# PA_stage_2.net
KiCad netlist of a schematic drawn in Altium Designer
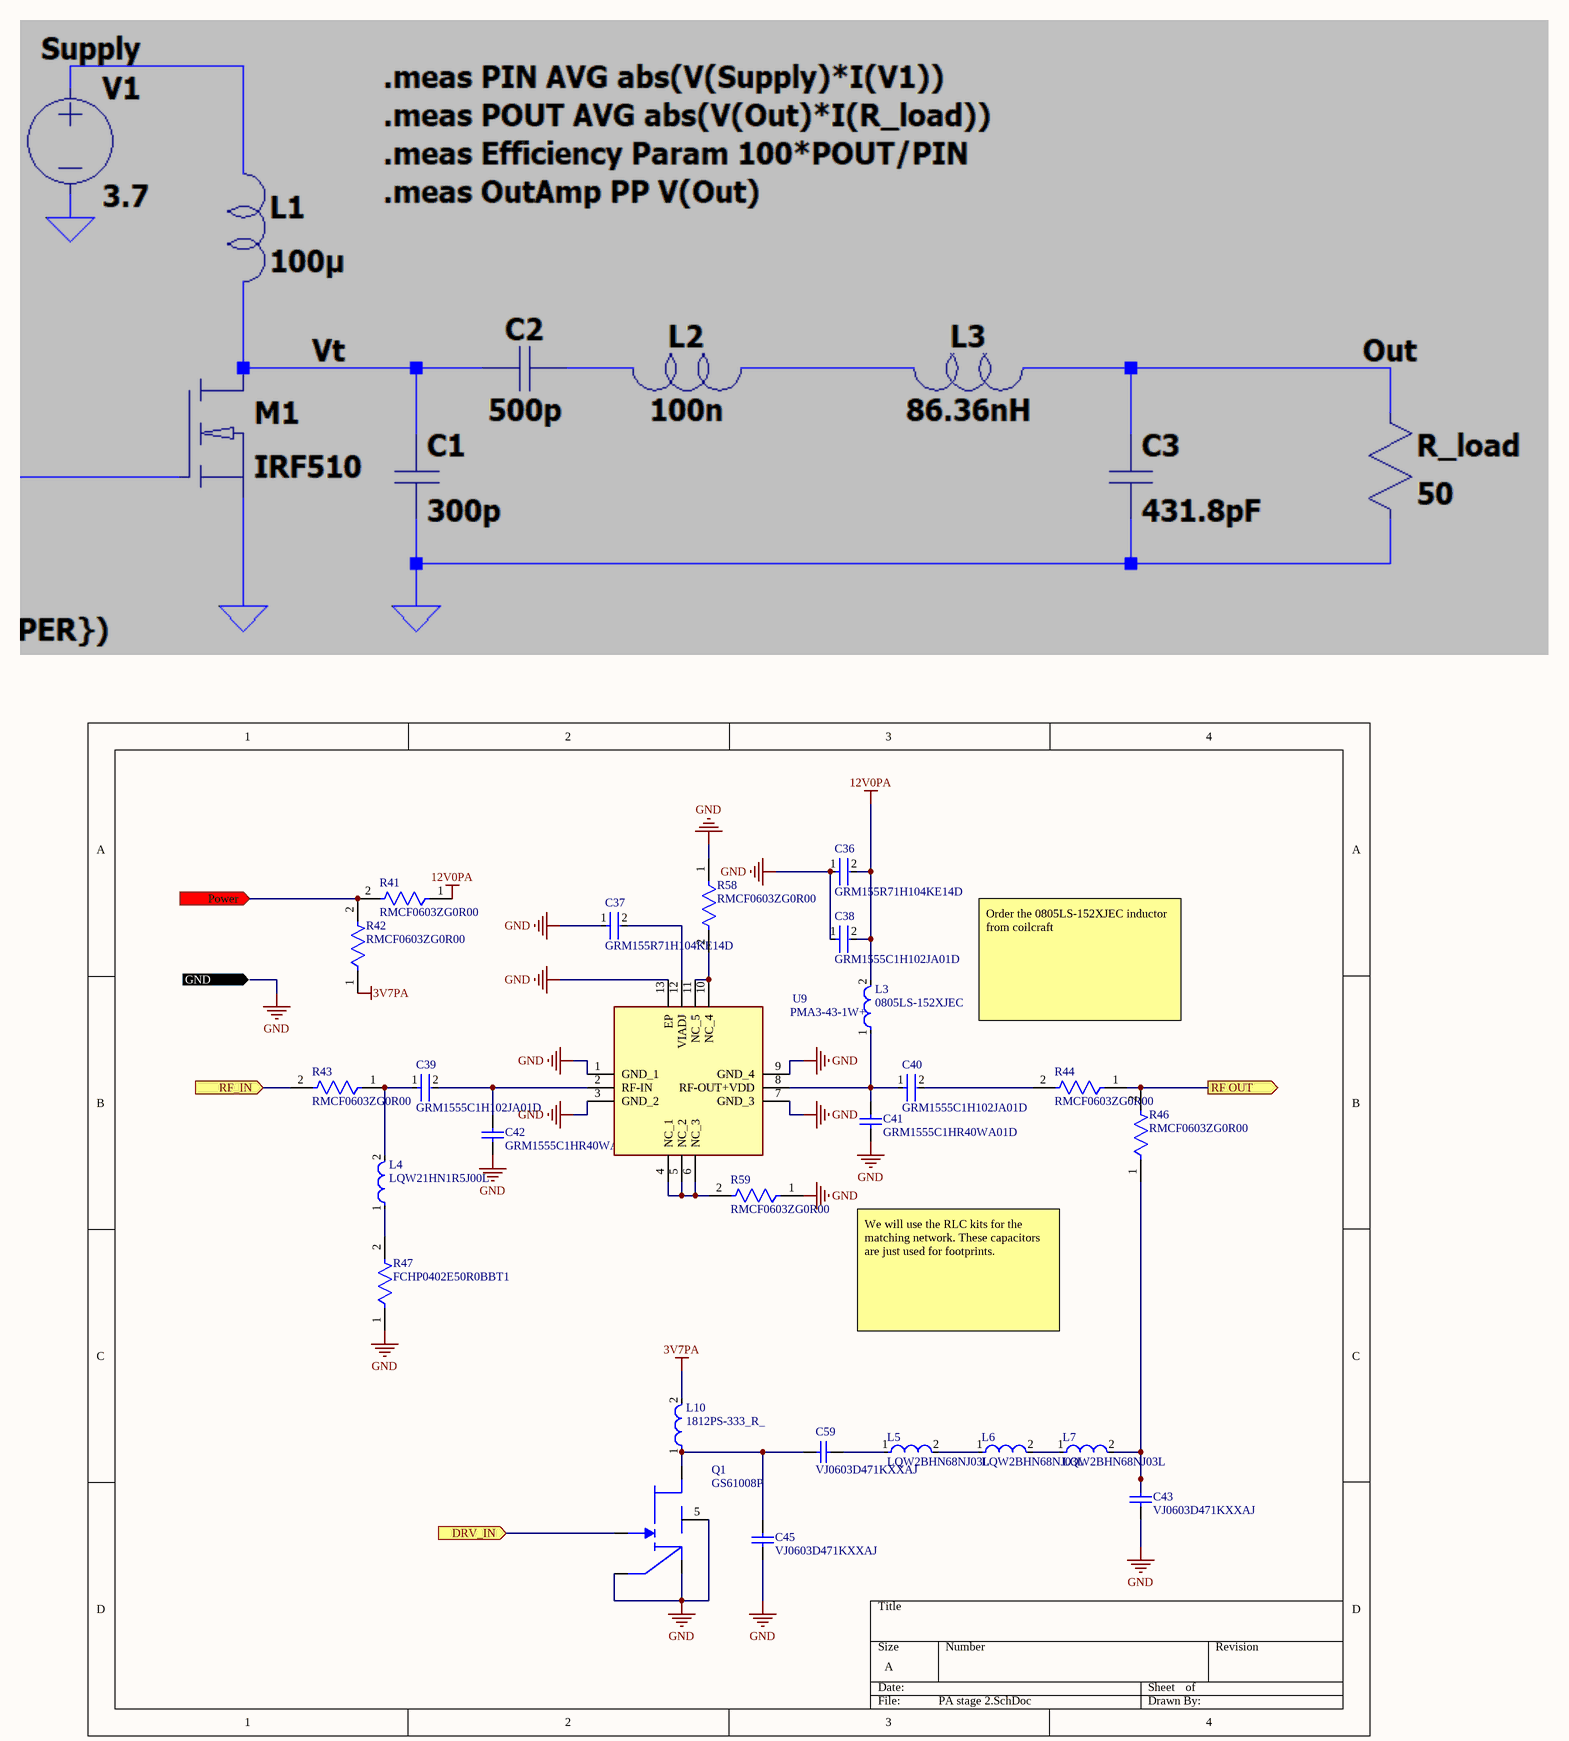
[diagram p0: PA stage 2.SchDoc]

(export (version "E")
  (design (tool "Eeschema 10.0.6"))
  (components
    (comp (ref "C36")
      (value "GRM155R71H104KE14D")
      (footprint "FP-GRM155-0_05-IPC_B")
      (description "Chip Multilayer Ceramic Capacitors for General Purpose, 0402, 0.10uF, X7R, 15%, 10%, 50V")
      (fields (field (name "VOLTAGE") "50V") (field (name "TOLERANCE") "10%"))
      (libsource (lib "Altium Content Vault") (part "02cd4be3c70576c341d710602a673aa"))
    )
    (comp (ref "C37")
      (value "GRM155R71H104KE14D")
      (footprint "FP-GRM155-0_05-IPC_B")
      (description "Chip Multilayer Ceramic Capacitors for General Purpose, 0402, 0.10uF, X7R, 15%, 10%, 50V")
      (fields (field (name "VOLTAGE") "50V") (field (name "TOLERANCE") "10%"))
      (libsource (lib "Altium Content Vault") (part "02cd4be3c70576c341d710602a673aa"))
    )
    (comp (ref "C38")
      (value "GRM1555C1H102JA01D")
      (footprint "FP-GRM155-0_05-IPC_B")
      (description "Chip Multilayer Ceramic Capacitors for General Purpose, 0402, 1000pF, C0G, 30ppm/°C, 5%, 50V")
      (fields (field (name "TOLERANCE") "5%") (field (name "VOLTAGE") "50V"))
      (libsource (lib "Altium Content Vault") (part "02cd4be3c70576c341d710602a673aa"))
    )
    (comp (ref "C39")
      (value "GRM1555C1H102JA01D")
      (footprint "FP-GRM155-0_05-IPC_B")
      (description "Chip Multilayer Ceramic Capacitors for General Purpose, 0402, 1000pF, C0G, 30ppm/°C, 5%, 50V")
      (fields (field (name "TOLERANCE") "5%") (field (name "VOLTAGE") "50V"))
      (libsource (lib "Altium Content Vault") (part "02cd4be3c70576c341d710602a673aa"))
    )
    (comp (ref "C40")
      (value "GRM1555C1H102JA01D")
      (footprint "FP-GRM155-0_05-IPC_B")
      (description "Chip Multilayer Ceramic Capacitors for General Purpose, 0402, 1000pF, C0G, 30ppm/°C, 5%, 50V")
      (fields (field (name "TOLERANCE") "5%") (field (name "VOLTAGE") "50V"))
      (libsource (lib "Altium Content Vault") (part "02cd4be3c70576c341d710602a673aa"))
    )
    (comp (ref "C41")
      (value "GRM1555C1HR40WA01D")
      (footprint "CAPC1005X55X25LL05T10")
      (fields (field (name "MANUFACTURER") "Murata"))
      (libsource (lib "Altium Content Vault") (part "CAP"))
    )
    (comp (ref "C42")
      (value "GRM1555C1HR40WA01D")
      (footprint "CAPC1005X55X25LL05T10")
      (fields (field (name "MANUFACTURER") "Murata"))
      (libsource (lib "Altium Content Vault") (part "CAP"))
    )
    (comp (ref "C43")
      (value "VJ0603D471KXXAJ")
      (footprint "CAPC1608X92X38LL15T08")
      (fields (field (name "MANUFACTURER") "Vitramon"))
      (libsource (lib "Altium Content Vault") (part "CAP"))
    )
    (comp (ref "C45")
      (value "VJ0603D471KXXAJ")
      (footprint "CAPC1608X92X38LL15T08")
      (fields (field (name "MANUFACTURER") "Vitramon"))
      (libsource (lib "Altium Content Vault") (part "CAP"))
    )
    (comp (ref "C59")
      (value "VJ0603D471KXXAJ")
      (footprint "CAPC1608X92X38LL15T08")
      (fields (field (name "MANUFACTURER") "Vitramon"))
      (libsource (lib "Altium Content Vault") (part "CAP"))
    )
    (comp (ref "L3")
      (value "0805LS-152XJEC")
      (footprint "FP-LQW21HN_00-MFG")
      (description "0805LS-152XJEC Coilcraft")
      (fields (field (name "TOLERANCE") "5%"))
      (libsource (lib "Altium Content Vault") (part "725321dda6339637d4d059423bc1c3c"))
    )
    (comp (ref "L4")
      (value "LQW21HN1R5J00L")
      (footprint "FP-LQW21HN_00-MFG")
      (description "Wire Wound Ferrite type RF Inuctor 1.5uH ±5% 85mA 5.33Ω 0805 (2012)")
      (fields (field (name "TOLERANCE") "5%"))
      (libsource (lib "Altium Content Vault") (part "725321dda6339637d4d059423bc1c3c"))
    )
    (comp (ref "L5")
      (value "LQW2BHN68NJ03L")
      (footprint "FP-LQW2BHN_03-MFG")
      (description "Wire Wound RF Inductor 68nH ±5% 460mA 0.23Ω 0805 (2015)")
      (fields (field (name "TOLERANCE") "5%"))
      (libsource (lib "Altium Content Vault") (part "725321dda6339637d4d059423bc1c3c"))
    )
    (comp (ref "L6")
      (value "LQW2BHN68NJ03L")
      (footprint "FP-LQW2BHN_03-MFG")
      (description "Wire Wound RF Inductor 68nH ±5% 460mA 0.23Ω 0805 (2015)")
      (fields (field (name "TOLERANCE") "5%"))
      (libsource (lib "Altium Content Vault") (part "725321dda6339637d4d059423bc1c3c"))
    )
    (comp (ref "L7")
      (value "LQW2BHN68NJ03L")
      (footprint "FP-LQW2BHN_03-MFG")
      (description "Wire Wound RF Inductor 68nH ±5% 460mA 0.23Ω 0805 (2015)")
      (fields (field (name "TOLERANCE") "5%"))
      (libsource (lib "Altium Content Vault") (part "725321dda6339637d4d059423bc1c3c"))
    )
    (comp (ref "L10")
      (value "1812PS-333_R_")
      (footprint "FP-1812PS-MFG")
      (description "1812PS-333_R_ Coilcraft")
      (fields (field (name "TOLERANCE") "5%"))
      (libsource (lib "Altium Content Vault") (part "725321dda6339637d4d059423bc1c3c"))
    )
    (comp (ref "Q1")
      (value "GS61008P")
      (footprint "TRANS_GS61008P")
      (description "Top cooled 100V enhancement mode GaN transistor")
      (fields (field (name "MF") "GaN Systems"))
      (libsource (lib "GS61008P") (part "GS61008P"))
    )
    (comp (ref "R41")
      (value "RMCF0603ZG0R00")
      (footprint "FP-RMCF0603-IPC_B")
      (description "0Ω ±0 0.1W 0603 Thick Film Chip Resistor AEC-Q200 compliant")
      (libsource (lib "Altium Content Vault") (part "1029c3af85768c4190bb7ad29bc67b5"))
    )
    (comp (ref "R42")
      (value "RMCF0603ZG0R00")
      (footprint "FP-RMCF0603-IPC_B")
      (description "0Ω ±0 0.1W 0603 Thick Film Chip Resistor AEC-Q200 compliant")
      (libsource (lib "Altium Content Vault") (part "1029c3af85768c4190bb7ad29bc67b5"))
    )
    (comp (ref "R43")
      (value "RMCF0603ZG0R00")
      (footprint "FP-RMCF0603-IPC_B")
      (description "0Ω ±0 0.1W 0603 Thick Film Chip Resistor AEC-Q200 compliant")
      (libsource (lib "Altium Content Vault") (part "1029c3af85768c4190bb7ad29bc67b5"))
    )
    (comp (ref "R44")
      (value "RMCF0603ZG0R00")
      (footprint "FP-RMCF0603-IPC_B")
      (description "0Ω ±0 0.1W 0603 Thick Film Chip Resistor AEC-Q200 compliant")
      (libsource (lib "Altium Content Vault") (part "1029c3af85768c4190bb7ad29bc67b5"))
    )
    (comp (ref "R46")
      (value "RMCF0603ZG0R00")
      (footprint "FP-RMCF0603-IPC_B")
      (description "0Ω ±0 0.1W 0603 Thick Film Chip Resistor AEC-Q200 compliant")
      (libsource (lib "Altium Content Vault") (part "1029c3af85768c4190bb7ad29bc67b5"))
    )
    (comp (ref "R47")
      (value "FCHP0402E50R0BBT1")
      (footprint "FP-FC0402-MFG")
      (fields (field (name "TOLERANCE") "0.1%"))
      (libsource (lib "Altium Content Vault") (part "1029c3af85768c4190bb7ad29bc67b5"))
    )
    (comp (ref "R58")
      (value "RMCF0603ZG0R00")
      (footprint "FP-RMCF0603-IPC_B")
      (description "0Ω ±0 0.1W 0603 Thick Film Chip Resistor AEC-Q200 compliant")
      (libsource (lib "Altium Content Vault") (part "1029c3af85768c4190bb7ad29bc67b5"))
    )
    (comp (ref "R59")
      (value "RMCF0603ZG0R00")
      (footprint "FP-RMCF0603-IPC_B")
      (description "0Ω ±0 0.1W 0603 Thick Film Chip Resistor AEC-Q200 compliant")
      (libsource (lib "Altium Content Vault") (part "1029c3af85768c4190bb7ad29bc67b5"))
    )
    (comp (ref "U9")
      (value "PMA3-43-1W+")
      (footprint "QFN51P300X300X89-13N")
      (description "Integrated Circuit")
      (libsource (lib "SamacSys") (part "PMA3-43-1W+"))
    )
  )
  (nets
    (net (code "1") (name "/DRV_IN") (class "Default")
      (node (ref "Q1") (pin "2") (pinfunction "G_2") (pintype "passive"))
    )
    (net (code "2") (name "/Power") (class "Default")
      (node (ref "R41") (pin "2") (pinfunction "2_2") (pintype "passive"))
      (node (ref "R42") (pin "2") (pinfunction "2_2") (pintype "passive"))
    )
    (net (code "3") (name "/RF OUT") (class "Default")
      (node (ref "R44") (pin "1") (pinfunction "1_1") (pintype "passive"))
      (node (ref "R46") (pin "2") (pinfunction "2_2") (pintype "passive"))
    )
    (net (code "4") (name "/RF_IN") (class "Default")
      (node (ref "R43") (pin "2") (pinfunction "2_2") (pintype "passive"))
    )
    (net (code "5") (name "3V7PA") (class "Default")
      (node (ref "L10") (pin "2") (pinfunction "2_2") (pintype "passive"))
      (node (ref "R42") (pin "1") (pinfunction "1_1") (pintype "passive"))
    )
    (net (code "6") (name "12V0PA") (class "Default")
      (node (ref "C36") (pin "2") (pinfunction "2_2") (pintype "passive"))
      (node (ref "C38") (pin "2") (pinfunction "2_2") (pintype "passive"))
      (node (ref "L3") (pin "2") (pinfunction "2_2") (pintype "passive"))
      (node (ref "R41") (pin "1") (pinfunction "1_1") (pintype "passive"))
    )
    (net (code "7") (name "GND") (class "Default")
      (node (ref "C36") (pin "1") (pinfunction "1_1") (pintype "passive"))
      (node (ref "C37") (pin "1") (pinfunction "1_1") (pintype "passive"))
      (node (ref "C38") (pin "1") (pinfunction "1_1") (pintype "passive"))
      (node (ref "C41") (pin "1") (pinfunction "1_1") (pintype "passive"))
      (node (ref "C42") (pin "1") (pinfunction "1_1") (pintype "passive"))
      (node (ref "C43") (pin "1") (pinfunction "1_1") (pintype "passive"))
      (node (ref "C45") (pin "1") (pinfunction "1_1") (pintype "passive"))
      (node (ref "Q1") (pin "3") (pinfunction "SS_3") (pintype "passive"))
      (node (ref "Q1") (pin "4") (pinfunction "S_4") (pintype "passive"))
      (node (ref "Q1") (pin "5") (pinfunction "THERMAL_PAD_5") (pintype "passive"))
      (node (ref "R47") (pin "1") (pinfunction "1_1") (pintype "passive"))
      (node (ref "R58") (pin "1") (pinfunction "1_1") (pintype "passive"))
      (node (ref "R59") (pin "1") (pinfunction "1_1") (pintype "passive"))
      (node (ref "U9") (pin "1") (pinfunction "GND_1_1") (pintype "passive"))
      (node (ref "U9") (pin "13") (pinfunction "EP_13") (pintype "passive"))
      (node (ref "U9") (pin "3") (pinfunction "GND_2_3") (pintype "passive"))
      (node (ref "U9") (pin "7") (pinfunction "GND_3_7") (pintype "passive"))
      (node (ref "U9") (pin "9") (pinfunction "GND_4_9") (pintype "passive"))
    )
    (net (code "8") (name "Net-(C39-Pad1)") (class "Default")
      (node (ref "C39") (pin "1") (pinfunction "1_1") (pintype "passive"))
      (node (ref "L4") (pin "2") (pinfunction "2_2") (pintype "passive"))
      (node (ref "R43") (pin "1") (pinfunction "1_1") (pintype "passive"))
    )
    (net (code "9") (name "Net-(C40-Pad2)") (class "Default")
      (node (ref "C40") (pin "2") (pinfunction "2_2") (pintype "passive"))
      (node (ref "R44") (pin "2") (pinfunction "2_2") (pintype "passive"))
    )
    (net (code "10") (name "Net-(C43-Pad2)") (class "Default")
      (node (ref "C43") (pin "2") (pinfunction "2_2") (pintype "passive"))
      (node (ref "L7") (pin "2") (pinfunction "2_2") (pintype "passive"))
      (node (ref "R46") (pin "1") (pinfunction "1_1") (pintype "passive"))
    )
    (net (code "11") (name "Net-(C59-Pad1)") (class "Default")
      (node (ref "C59") (pin "1") (pinfunction "1_1") (pintype "passive"))
      (node (ref "L5") (pin "1") (pinfunction "1_1") (pintype "passive"))
    )
    (net (code "12") (name "Net-(L4-Pad1)") (class "Default")
      (node (ref "L4") (pin "1") (pinfunction "1_1") (pintype "passive"))
      (node (ref "R47") (pin "2") (pinfunction "2_2") (pintype "passive"))
    )
    (net (code "13") (name "Net-(L5-Pad2)") (class "Default")
      (node (ref "L5") (pin "2") (pinfunction "2_2") (pintype "passive"))
      (node (ref "L6") (pin "1") (pinfunction "1_1") (pintype "passive"))
    )
    (net (code "14") (name "Net-(L6-Pad2)") (class "Default")
      (node (ref "L6") (pin "2") (pinfunction "2_2") (pintype "passive"))
      (node (ref "L7") (pin "1") (pinfunction "1_1") (pintype "passive"))
    )
    (net (code "15") (name "Net-(Q1-D)") (class "Default")
      (node (ref "C45") (pin "2") (pinfunction "2_2") (pintype "passive"))
      (node (ref "C59") (pin "2") (pinfunction "2_2") (pintype "passive"))
      (node (ref "L10") (pin "1") (pinfunction "1_1") (pintype "passive"))
      (node (ref "Q1") (pin "1") (pinfunction "D_1") (pintype "passive"))
    )
    (net (code "16") (name "Net-(U9-NC_1)") (class "Default")
      (node (ref "R59") (pin "2") (pinfunction "2_2") (pintype "passive"))
      (node (ref "U9") (pin "4") (pinfunction "NC_1_4") (pintype "passive"))
      (node (ref "U9") (pin "5") (pinfunction "NC_2_5") (pintype "passive"))
      (node (ref "U9") (pin "6") (pinfunction "NC_3_6") (pintype "passive"))
    )
    (net (code "17") (name "Net-(U9-NC_4)") (class "Default")
      (node (ref "R58") (pin "2") (pinfunction "2_2") (pintype "passive"))
      (node (ref "U9") (pin "10") (pinfunction "NC_4_10") (pintype "passive"))
      (node (ref "U9") (pin "11") (pinfunction "NC_5_11") (pintype "passive"))
    )
    (net (code "18") (name "Net-(U9-RF-IN)") (class "Default")
      (node (ref "C39") (pin "2") (pinfunction "2_2") (pintype "passive"))
      (node (ref "C42") (pin "2") (pinfunction "2_2") (pintype "passive"))
      (node (ref "U9") (pin "2") (pinfunction "RF-IN_2") (pintype "passive"))
    )
    (net (code "19") (name "Net-(U9-RF-OUT+VDD)") (class "Default")
      (node (ref "C40") (pin "1") (pinfunction "1_1") (pintype "passive"))
      (node (ref "C41") (pin "2") (pinfunction "2_2") (pintype "passive"))
      (node (ref "L3") (pin "1") (pinfunction "1_1") (pintype "passive"))
      (node (ref "U9") (pin "8") (pinfunction "RF-OUT+VDD_8") (pintype "passive"))
    )
    (net (code "20") (name "Net-(U9-VIADJ)") (class "Default")
      (node (ref "C37") (pin "2") (pinfunction "2_2") (pintype "passive"))
      (node (ref "U9") (pin "12") (pinfunction "VIADJ_12") (pintype "passive"))
    )
  )
)
